# picoAva.net
KiCad netlist of a schematic drawn in EAGLE
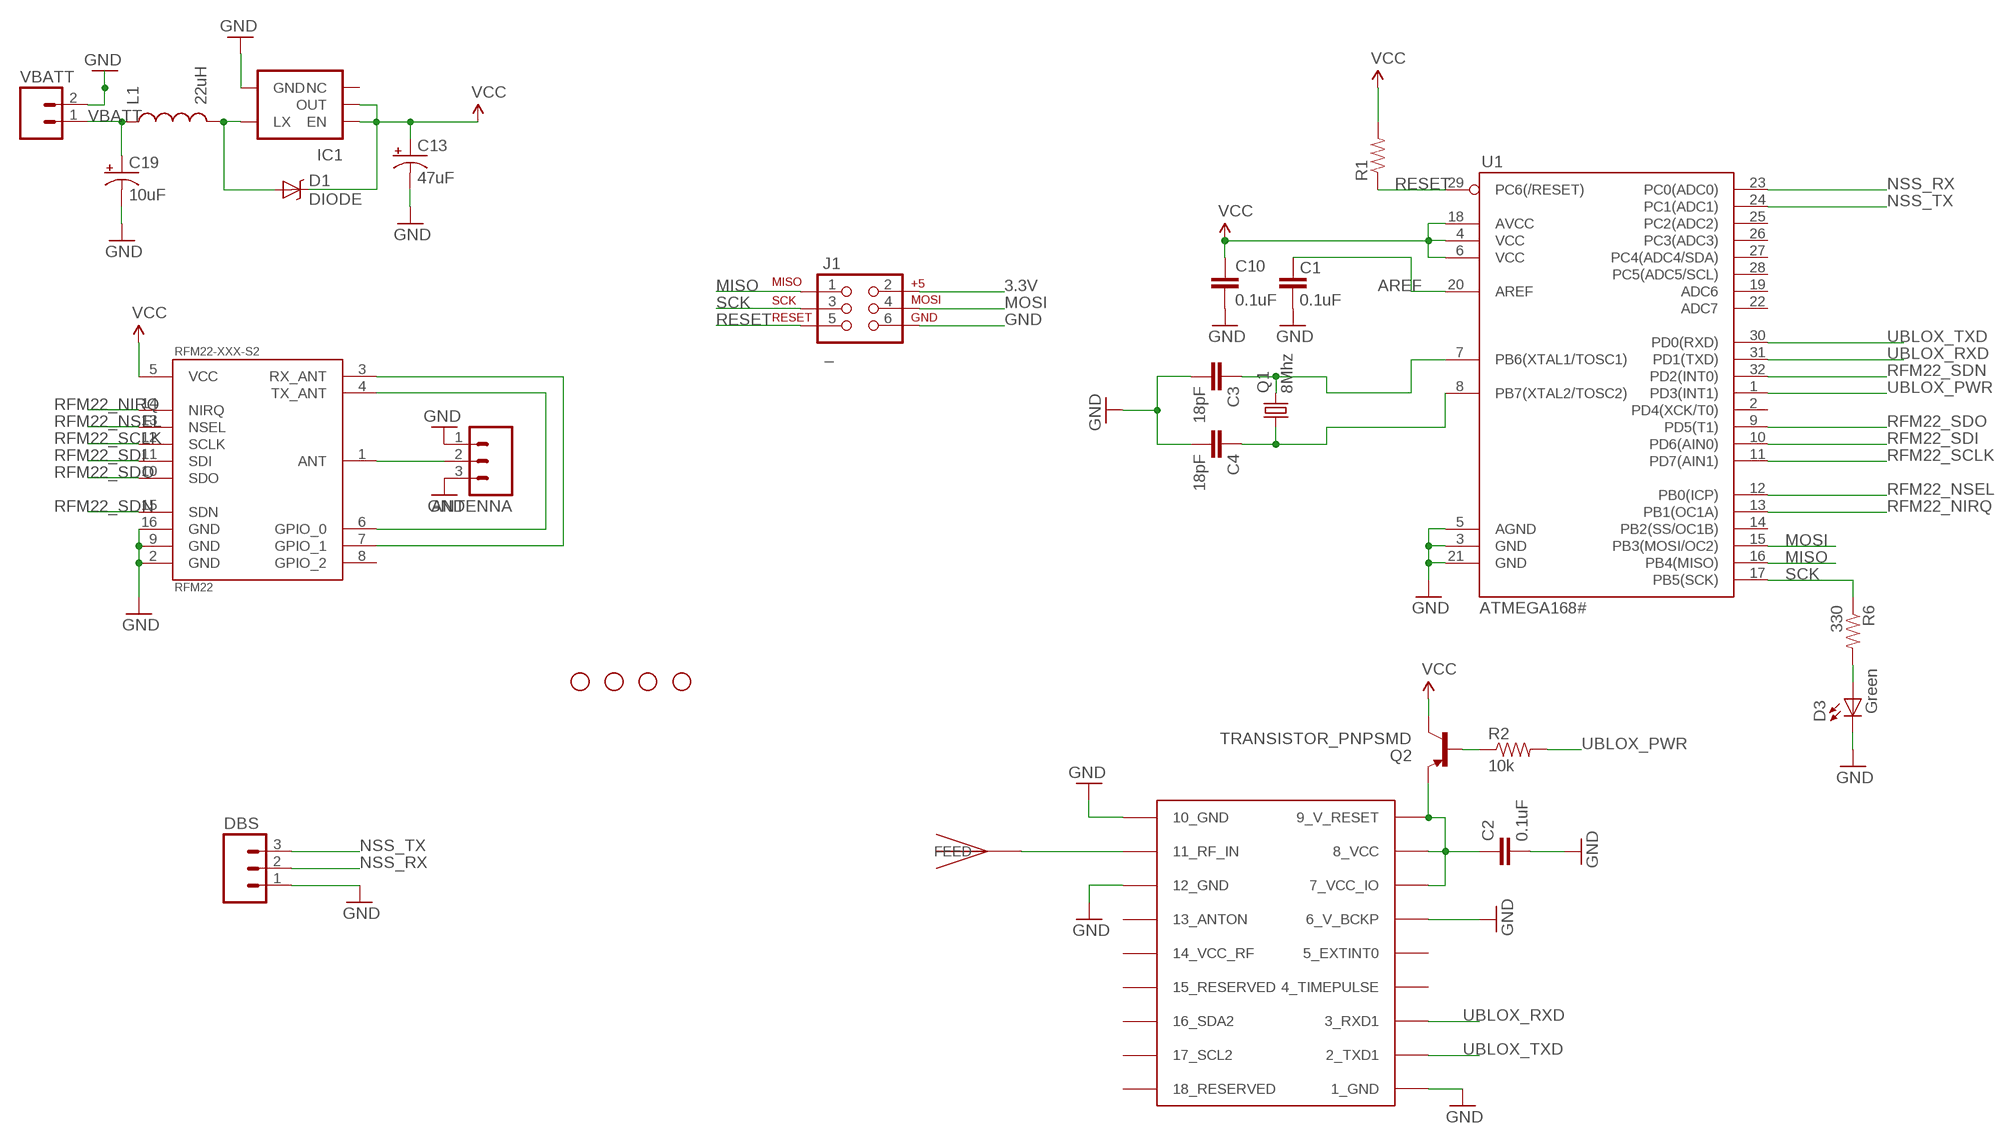
[diagram p0: schematic, sheet 1]

(export (version "E")
  (design (tool "Eeschema 10.0.6"))
  (components
    (comp (ref "ANTENNA")
      (value "M03PTH")
      (footprint "eagle-import:1X03")
      (libsource (lib "eagle-import") (part "M03PTH"))
    )
    (comp (ref "C1")
      (value "0.1uF")
      (footprint "eagle-import:0603-CAP")
      (libsource (lib "eagle-import") (part "CAP0603-CAP"))
    )
    (comp (ref "C2")
      (value "0.1uF")
      (footprint "eagle-import:0603-CAP")
      (libsource (lib "eagle-import") (part "CAP0603-CAP"))
    )
    (comp (ref "C3")
      (value "18pF")
      (footprint "eagle-import:C0805")
      (libsource (lib "eagle-import") (part "C-EUC0805"))
    )
    (comp (ref "C4")
      (value "18pF")
      (footprint "eagle-import:C0805")
      (libsource (lib "eagle-import") (part "C-EUC0805"))
    )
    (comp (ref "C10")
      (value "0.1uF")
      (footprint "eagle-import:0603-CAP")
      (libsource (lib "eagle-import") (part "CAP0603-CAP"))
    )
    (comp (ref "C13")
      (value "47uF")
      (footprint "eagle-import:EIA3216")
      (libsource (lib "eagle-import") (part "CAP_POL1206"))
    )
    (comp (ref "C19")
      (value "10uF")
      (footprint "eagle-import:EIA3216")
      (libsource (lib "eagle-import") (part "CAP_POL1206"))
    )
    (comp (ref "D1")
      (value "DIODE")
      (footprint "eagle-import:SMA-DIODE")
      (libsource (lib "eagle-import") (part "DIODE-SCHOTTKY_"))
    )
    (comp (ref "D3")
      (value "Green")
      (footprint "eagle-import:LED-0603")
      (libsource (lib "eagle-import") (part "LED0603"))
    )
    (comp (ref "DBS")
      (value "M03PTH")
      (footprint "eagle-import:1X03")
      (libsource (lib "eagle-import") (part "M03PTH"))
    )
    (comp (ref "IC1")
      (value "V_REG_NCP1400SOT23-5")
      (footprint "eagle-import:SOT23-5")
      (libsource (lib "eagle-import") (part "V_REG_NCP1400SOT23-5"))
    )
    (comp (ref "J1")
      (value "_")
      (footprint "eagle-import:2X3-NS")
      (libsource (lib "eagle-import") (part "AVR_SPI_PRG_6NS"))
    )
    (comp (ref "JP1")
      (value "STAND-OFF")
      (footprint "eagle-import:STAND-OFF")
      (libsource (lib "eagle-import") (part "STAND-OFF"))
    )
    (comp (ref "JP2")
      (value "STAND-OFF")
      (footprint "eagle-import:STAND-OFF")
      (libsource (lib "eagle-import") (part "STAND-OFF"))
    )
    (comp (ref "JP3")
      (value "STAND-OFF")
      (footprint "eagle-import:STAND-OFF")
      (libsource (lib "eagle-import") (part "STAND-OFF"))
    )
    (comp (ref "JP4")
      (value "STAND-OFF")
      (footprint "eagle-import:STAND-OFF")
      (libsource (lib "eagle-import") (part "STAND-OFF"))
    )
    (comp (ref "L1")
      (value "22uH")
      (footprint "eagle-import:1210")
      (libsource (lib "eagle-import") (part "INDUCTOR1210"))
    )
    (comp (ref "Q1")
      (value "8Mhz")
      (footprint "eagle-import:HC49UP")
      (libsource (lib "eagle-import") (part "CRYSTALSMD"))
    )
    (comp (ref "Q2")
      (value "TRANSISTOR_PNPSMD")
      (footprint "eagle-import:SOT23-3")
      (libsource (lib "eagle-import") (part "TRANSISTOR_PNPSMD"))
    )
    (comp (ref "R1")
      (value "RESISTOR0603-RES")
      (footprint "eagle-import:0603-RES")
      (libsource (lib "eagle-import") (part "RESISTOR0603-RES"))
    )
    (comp (ref "R2")
      (value "10k")
      (footprint "eagle-import:0603-RES")
      (libsource (lib "eagle-import") (part "RESISTOR0603-RES"))
    )
    (comp (ref "R6")
      (value "330")
      (footprint "eagle-import:0603-RES")
      (libsource (lib "eagle-import") (part "RESISTOR0603-RES"))
    )
    (comp (ref "RFM22-XXX-S2")
      (value "RFM22")
      (footprint "eagle-import:RFM22-XXX-S2")
      (libsource (lib "eagle-import") (part "RFM22"))
    )
    (comp (ref "U$1")
      (value "UBLOX_MAX-6")
      (footprint "eagle-import:UBLOX_MAX-6")
      (libsource (lib "eagle-import") (part "UBLOX_MAX-6"))
    )
    (comp (ref "U$3")
      (value "JTI_ANTENNA-1575AT43A40")
      (footprint "eagle-import:JTI_ANTENNA-1575AT43A40")
      (libsource (lib "eagle-import") (part "JTI_ANTENNA-1575AT43A40"))
    )
    (comp (ref "U1")
      (value "ATMEGA168#")
      (footprint "eagle-import:TQFP32-08")
      (libsource (lib "eagle-import") (part "ATMEGA168"))
    )
    (comp (ref "VBATT")
      (value "M02PTH")
      (footprint "eagle-import:1X02")
      (libsource (lib "eagle-import") (part "M02PTH"))
    )
  )
  (nets
    (net (code "1") (name "3.3V") (class "Default")
      (node (ref "C10") (pin "1") (pinfunction "1_1") (pintype "passive"))
      (node (ref "C13") (pin "A") (pinfunction "+_A") (pintype "passive"))
      (node (ref "D1") (pin "C") (pinfunction "C_C") (pintype "passive"))
      (node (ref "IC1") (pin "1") (pinfunction "EN_1") (pintype "input"))
      (node (ref "IC1") (pin "2") (pinfunction "OUT_2") (pintype "passive"))
      (node (ref "J1") (pin "2") (pinfunction "2_2") (pintype "passive"))
      (node (ref "Q2") (pin "3") (pinfunction "C_3") (pintype "passive"))
      (node (ref "R1") (pin "2") (pinfunction "2_2") (pintype "passive"))
      (node (ref "RFM22-XXX-S2") (pin "5") (pinfunction "VCC_5") (pintype "bidirectional"))
      (node (ref "U1") (pin "18") (pinfunction "AVCC_18") (pintype "bidirectional"))
      (node (ref "U1") (pin "4") (pinfunction "VCC_4") (pintype "bidirectional"))
      (node (ref "U1") (pin "6") (pinfunction "VCC_6") (pintype "bidirectional"))
    )
    (net (code "2") (name "AREF") (class "Default")
      (node (ref "C1") (pin "2") (pinfunction "2_2") (pintype "passive"))
      (node (ref "U1") (pin "20") (pinfunction "AREF_20") (pintype "bidirectional"))
    )
    (net (code "3") (name "GND") (class "Default")
      (node (ref "ANTENNA") (pin "1") (pinfunction "1_1") (pintype "passive"))
      (node (ref "ANTENNA") (pin "3") (pinfunction "3_3") (pintype "passive"))
      (node (ref "C1") (pin "1") (pinfunction "1_1") (pintype "passive"))
      (node (ref "C10") (pin "2") (pinfunction "2_2") (pintype "passive"))
      (node (ref "C13") (pin "C") (pinfunction "-_C") (pintype "passive"))
      (node (ref "C19") (pin "C") (pinfunction "-_C") (pintype "passive"))
      (node (ref "C2") (pin "2") (pinfunction "2_2") (pintype "passive"))
      (node (ref "C3") (pin "2") (pinfunction "2_2") (pintype "passive"))
      (node (ref "C4") (pin "2") (pinfunction "2_2") (pintype "passive"))
      (node (ref "D3") (pin "C") (pinfunction "C_C") (pintype "passive"))
      (node (ref "DBS") (pin "1") (pinfunction "1_1") (pintype "passive"))
      (node (ref "IC1") (pin "4") (pinfunction "GND_4") (pintype "input"))
      (node (ref "J1") (pin "6") (pinfunction "6_6") (pintype "passive"))
      (node (ref "RFM22-XXX-S2") (pin "16") (pinfunction "GND_16") (pintype "power_in"))
      (node (ref "RFM22-XXX-S2") (pin "2") (pinfunction "GND_2") (pintype "power_in"))
      (node (ref "RFM22-XXX-S2") (pin "9") (pinfunction "GND_9") (pintype "power_in"))
      (node (ref "U$1") (pin "10_GND") (pinfunction "10_GND_10_GND") (pintype "bidirectional"))
      (node (ref "U$1") (pin "12_GND") (pinfunction "12_GND_12_GND") (pintype "bidirectional"))
      (node (ref "U$1") (pin "1_GND") (pinfunction "1_GND_1_GND") (pintype "bidirectional"))
      (node (ref "U$1") (pin "6_V_BCKP") (pinfunction "6_V_BCKP_6_V_BCKP") (pintype "bidirectional"))
      (node (ref "U1") (pin "21") (pinfunction "GND_21") (pintype "bidirectional"))
      (node (ref "U1") (pin "3") (pinfunction "GND_3") (pintype "bidirectional"))
      (node (ref "U1") (pin "5") (pinfunction "AGND_5") (pintype "bidirectional"))
      (node (ref "VBATT") (pin "2") (pinfunction "2_2") (pintype "passive"))
    )
    (net (code "4") (name "MISO") (class "Default")
      (node (ref "J1") (pin "1") (pinfunction "1_1") (pintype "passive"))
      (node (ref "U1") (pin "16") (pinfunction "PB4(MISO)_16") (pintype "bidirectional"))
    )
    (net (code "5") (name "MOSI") (class "Default")
      (node (ref "J1") (pin "4") (pinfunction "4_4") (pintype "passive"))
      (node (ref "U1") (pin "15") (pinfunction "PB3(MOSI/OC2)_15") (pintype "bidirectional"))
    )
    (net (code "6") (name "NSS_RX") (class "Default")
      (node (ref "DBS") (pin "2") (pinfunction "2_2") (pintype "passive"))
      (node (ref "U1") (pin "23") (pinfunction "PC0(ADC0)_23") (pintype "bidirectional"))
    )
    (net (code "7") (name "NSS_TX") (class "Default")
      (node (ref "DBS") (pin "3") (pinfunction "3_3") (pintype "passive"))
      (node (ref "U1") (pin "24") (pinfunction "PC1(ADC1)_24") (pintype "bidirectional"))
    )
    (net (code "8") (name "Net-(D3-PadA)") (class "Default")
      (node (ref "D3") (pin "A") (pinfunction "A_A") (pintype "passive"))
      (node (ref "R6") (pin "2") (pinfunction "2_2") (pintype "passive"))
    )
    (net (code "9") (name "Net-(IC1-LX)") (class "Default")
      (node (ref "D1") (pin "A") (pinfunction "A_A") (pintype "passive"))
      (node (ref "IC1") (pin "5") (pinfunction "LX_5") (pintype "input"))
      (node (ref "L1") (pin "2") (pinfunction "2_2") (pintype "passive"))
    )
    (net (code "10") (name "Net-(Q2-B)") (class "Default")
      (node (ref "Q2") (pin "1") (pinfunction "B_1") (pintype "passive"))
      (node (ref "R2") (pin "1") (pinfunction "1_1") (pintype "passive"))
    )
    (net (code "11") (name "Net-(Q2-E)") (class "Default")
      (node (ref "C2") (pin "1") (pinfunction "1_1") (pintype "passive"))
      (node (ref "Q2") (pin "2") (pinfunction "E_2") (pintype "passive"))
      (node (ref "U$1") (pin "7_VCC_IO") (pinfunction "7_VCC_IO_7_VCC_IO") (pintype "bidirectional"))
      (node (ref "U$1") (pin "8_VCC") (pinfunction "8_VCC_8_VCC") (pintype "bidirectional"))
      (node (ref "U$1") (pin "9_V_RESET") (pinfunction "9_V_RESET_9_V_RESET") (pintype "bidirectional"))
    )
    (net (code "12") (name "Net-(RFM22-XXX-S2-ANT)") (class "Default")
      (node (ref "ANTENNA") (pin "2") (pinfunction "2_2") (pintype "passive"))
      (node (ref "RFM22-XXX-S2") (pin "1") (pinfunction "ANT_1") (pintype "bidirectional"))
    )
    (net (code "13") (name "Net-(RFM22-XXX-S2-GPIO_0)") (class "Default")
      (node (ref "RFM22-XXX-S2") (pin "4") (pinfunction "TX_ANT_4") (pintype "input"))
      (node (ref "RFM22-XXX-S2") (pin "6") (pinfunction "GPIO_0_6") (pintype "bidirectional"))
    )
    (net (code "14") (name "Net-(RFM22-XXX-S2-GPIO_1)") (class "Default")
      (node (ref "RFM22-XXX-S2") (pin "3") (pinfunction "RX_ANT_3") (pintype "input"))
      (node (ref "RFM22-XXX-S2") (pin "7") (pinfunction "GPIO_1_7") (pintype "bidirectional"))
    )
    (net (code "15") (name "Net-(U$1-Pad11_RF_IN)") (class "Default")
      (node (ref "U$1") (pin "11_RF_IN") (pinfunction "11_RF_IN_11_RF_IN") (pintype "bidirectional"))
      (node (ref "U$3") (pin "FEED") (pinfunction "FEED_FEED") (pintype "bidirectional"))
    )
    (net (code "16") (name "Net-(U1-PB6(XTAL1{slash}TOSC1))") (class "Default")
      (node (ref "C3") (pin "1") (pinfunction "1_1") (pintype "passive"))
      (node (ref "Q1") (pin "2") (pinfunction "2_2") (pintype "passive"))
      (node (ref "U1") (pin "7") (pinfunction "PB6(XTAL1/TOSC1)_7") (pintype "bidirectional"))
    )
    (net (code "17") (name "Net-(U1-PB7(XTAL2{slash}TOSC2))") (class "Default")
      (node (ref "C4") (pin "1") (pinfunction "1_1") (pintype "passive"))
      (node (ref "Q1") (pin "1") (pinfunction "1_1") (pintype "passive"))
      (node (ref "U1") (pin "8") (pinfunction "PB7(XTAL2/TOSC2)_8") (pintype "bidirectional"))
    )
    (net (code "18") (name "RESET") (class "Default")
      (node (ref "J1") (pin "5") (pinfunction "5_5") (pintype "passive"))
      (node (ref "R1") (pin "1") (pinfunction "1_1") (pintype "passive"))
      (node (ref "U1") (pin "29") (pinfunction "PC6(/RESET)_29") (pintype "bidirectional"))
    )
    (net (code "19") (name "RFM22_NIRQ") (class "Default")
      (node (ref "RFM22-XXX-S2") (pin "14") (pinfunction "NIRQ_14") (pintype "output"))
      (node (ref "U1") (pin "13") (pinfunction "PB1(OC1A)_13") (pintype "bidirectional"))
    )
    (net (code "20") (name "RFM22_NSEL") (class "Default")
      (node (ref "RFM22-XXX-S2") (pin "13") (pinfunction "NSEL_13") (pintype "input"))
      (node (ref "U1") (pin "12") (pinfunction "PB0(ICP)_12") (pintype "bidirectional"))
    )
    (net (code "21") (name "RFM22_SCLK") (class "Default")
      (node (ref "RFM22-XXX-S2") (pin "12") (pinfunction "SCLK_12") (pintype "input"))
      (node (ref "U1") (pin "11") (pinfunction "PD7(AIN1)_11") (pintype "bidirectional"))
    )
    (net (code "22") (name "RFM22_SDI") (class "Default")
      (node (ref "RFM22-XXX-S2") (pin "11") (pinfunction "SDI_11") (pintype "input"))
      (node (ref "U1") (pin "10") (pinfunction "PD6(AIN0)_10") (pintype "bidirectional"))
    )
    (net (code "23") (name "RFM22_SDN") (class "Default")
      (node (ref "RFM22-XXX-S2") (pin "15") (pinfunction "SDN_15") (pintype "input"))
      (node (ref "U1") (pin "32") (pinfunction "PD2(INT0)_32") (pintype "bidirectional"))
    )
    (net (code "24") (name "RFM22_SDO") (class "Default")
      (node (ref "RFM22-XXX-S2") (pin "10") (pinfunction "SDO_10") (pintype "output"))
      (node (ref "U1") (pin "9") (pinfunction "PD5(T1)_9") (pintype "bidirectional"))
    )
    (net (code "25") (name "SCK") (class "Default")
      (node (ref "J1") (pin "3") (pinfunction "3_3") (pintype "passive"))
      (node (ref "R6") (pin "1") (pinfunction "1_1") (pintype "passive"))
      (node (ref "U1") (pin "17") (pinfunction "PB5(SCK)_17") (pintype "bidirectional"))
    )
    (net (code "26") (name "UBLOX_PWR") (class "Default")
      (node (ref "R2") (pin "2") (pinfunction "2_2") (pintype "passive"))
      (node (ref "U1") (pin "1") (pinfunction "PD3(INT1)_1") (pintype "bidirectional"))
    )
    (net (code "27") (name "UBLOX_RXD") (class "Default")
      (node (ref "U$1") (pin "3_RXD1") (pinfunction "3_RXD1_3_RXD1") (pintype "bidirectional"))
      (node (ref "U1") (pin "31") (pinfunction "PD1(TXD)_31") (pintype "bidirectional"))
    )
    (net (code "28") (name "UBLOX_TXD") (class "Default")
      (node (ref "U$1") (pin "2_TXD1") (pinfunction "2_TXD1_2_TXD1") (pintype "bidirectional"))
      (node (ref "U1") (pin "30") (pinfunction "PD0(RXD)_30") (pintype "bidirectional"))
    )
    (net (code "29") (name "VBATT") (class "Default")
      (node (ref "C19") (pin "A") (pinfunction "+_A") (pintype "passive"))
      (node (ref "L1") (pin "1") (pinfunction "1_1") (pintype "passive"))
      (node (ref "VBATT") (pin "1") (pinfunction "1_1") (pintype "passive"))
    )
    (net (code "30") (name "unconnected-(IC1-NC-Pad3)") (class "Default")
      (node (ref "IC1") (pin "3") (pinfunction "NC_3") (pintype "input"))
    )
    (net (code "31") (name "unconnected-(RFM22-XXX-S2-GPIO_2-Pad8)") (class "Default")
      (node (ref "RFM22-XXX-S2") (pin "8") (pinfunction "GPIO_2_8") (pintype "bidirectional"))
    )
    (net (code "32") (name "unconnected-(U$1-Pad4_TIMEPULSE)") (class "Default")
      (node (ref "U$1") (pin "4_TIMEPULSE") (pinfunction "4_TIMEPULSE_4_TIMEPULSE") (pintype "bidirectional"))
    )
    (net (code "33") (name "unconnected-(U$1-Pad5_EXTINT0)") (class "Default")
      (node (ref "U$1") (pin "5_EXTINT0") (pinfunction "5_EXTINT0_5_EXTINT0") (pintype "bidirectional"))
    )
    (net (code "34") (name "unconnected-(U$1-Pad13_ANTON)") (class "Default")
      (node (ref "U$1") (pin "13_ANTON") (pinfunction "13_ANTON_13_ANTON") (pintype "bidirectional"))
    )
    (net (code "35") (name "unconnected-(U$1-Pad14_VCC_RF)") (class "Default")
      (node (ref "U$1") (pin "14_VCC_RF") (pinfunction "14_VCC_RF_14_VCC_RF") (pintype "bidirectional"))
    )
    (net (code "36") (name "unconnected-(U$1-Pad15_RESERVED)") (class "Default")
      (node (ref "U$1") (pin "15_RESERVED") (pinfunction "15_RESERVED_15_RESERVED") (pintype "bidirectional"))
    )
    (net (code "37") (name "unconnected-(U$1-Pad16_SDA2)") (class "Default")
      (node (ref "U$1") (pin "16_SDA2") (pinfunction "16_SDA2_16_SDA2") (pintype "bidirectional"))
    )
    (net (code "38") (name "unconnected-(U$1-Pad17_SCL2)") (class "Default")
      (node (ref "U$1") (pin "17_SCL2") (pinfunction "17_SCL2_17_SCL2") (pintype "bidirectional"))
    )
    (net (code "39") (name "unconnected-(U$1-Pad18_RESERVED)") (class "Default")
      (node (ref "U$1") (pin "18_RESERVED") (pinfunction "18_RESERVED_18_RESERVED") (pintype "bidirectional"))
    )
    (net (code "40") (name "unconnected-(U1-ADC6-Pad19)") (class "Default")
      (node (ref "U1") (pin "19") (pinfunction "ADC6_19") (pintype "bidirectional"))
    )
    (net (code "41") (name "unconnected-(U1-ADC7-Pad22)") (class "Default")
      (node (ref "U1") (pin "22") (pinfunction "ADC7_22") (pintype "bidirectional"))
    )
    (net (code "42") (name "unconnected-(U1-PB2(SS{slash}OC1B)-Pad14)") (class "Default")
      (node (ref "U1") (pin "14") (pinfunction "PB2(SS/OC1B)_14") (pintype "bidirectional"))
    )
    (net (code "43") (name "unconnected-(U1-PC2(ADC2)-Pad25)") (class "Default")
      (node (ref "U1") (pin "25") (pinfunction "PC2(ADC2)_25") (pintype "bidirectional"))
    )
    (net (code "44") (name "unconnected-(U1-PC3(ADC3)-Pad26)") (class "Default")
      (node (ref "U1") (pin "26") (pinfunction "PC3(ADC3)_26") (pintype "bidirectional"))
    )
    (net (code "45") (name "unconnected-(U1-PC4(ADC4{slash}SDA)-Pad27)") (class "Default")
      (node (ref "U1") (pin "27") (pinfunction "PC4(ADC4/SDA)_27") (pintype "bidirectional"))
    )
    (net (code "46") (name "unconnected-(U1-PC5(ADC5{slash}SCL)-Pad28)") (class "Default")
      (node (ref "U1") (pin "28") (pinfunction "PC5(ADC5/SCL)_28") (pintype "bidirectional"))
    )
    (net (code "47") (name "unconnected-(U1-PD4(XCK{slash}T0)-Pad2)") (class "Default")
      (node (ref "U1") (pin "2") (pinfunction "PD4(XCK/T0)_2") (pintype "bidirectional"))
    )
  )
)
